# attiny_pico.net
KiCad netlist of a schematic drawn in EAGLE
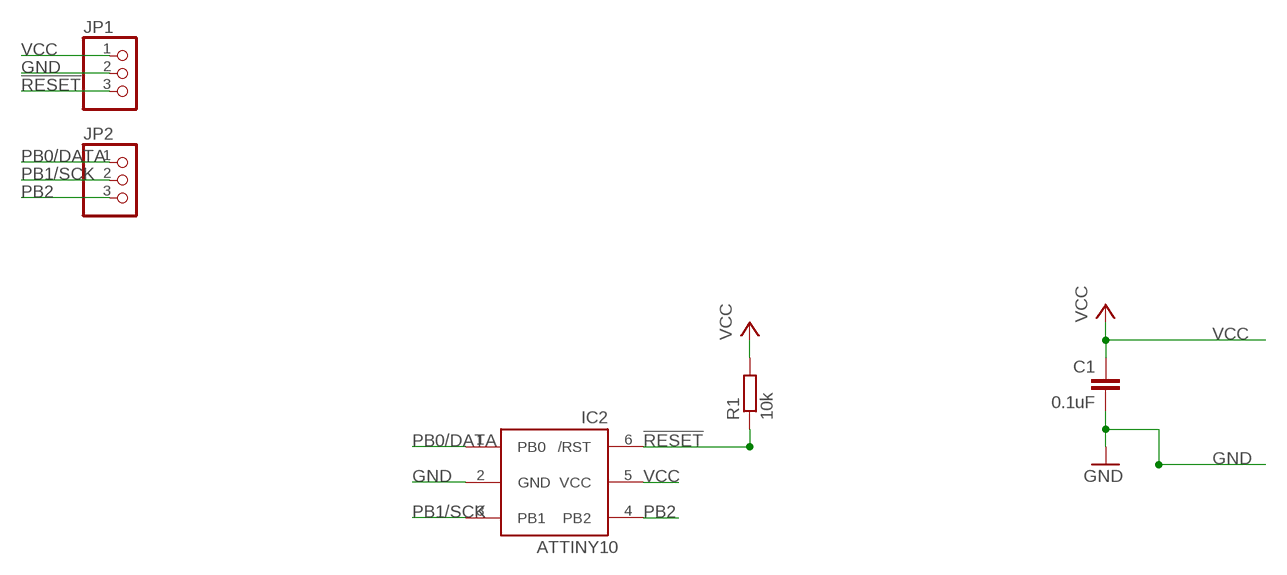
[diagram p0: schematic, sheet 1]

(export (version "E")
  (design (tool "Eeschema 10.0.6"))
  (components
    (comp (ref "C1")
      (value "0.1uF")
      (footprint "eagle-import:C0805")
      (libsource (lib "eagle-import") (part "C-EUC0805"))
    )
    (comp (ref "IC2")
      (value "ATTINY10")
      (footprint "eagle-import:SOT23-6")
      (libsource (lib "eagle-import") (part "ATTINY10"))
    )
    (comp (ref "JP1")
      (value "PINHD-1X3")
      (footprint "eagle-import:1X03")
      (libsource (lib "eagle-import") (part "PINHD-1X3"))
    )
    (comp (ref "JP2")
      (value "PINHD-1X3")
      (footprint "eagle-import:1X03")
      (libsource (lib "eagle-import") (part "PINHD-1X3"))
    )
    (comp (ref "R1")
      (value "10k")
      (footprint "eagle-import:R0805")
      (libsource (lib "eagle-import") (part "R-EU_R0805"))
    )
  )
  (nets
    (net (code "1") (name "/PB0{slash}DATA") (class "Default")
      (node (ref "IC2") (pin "1") (pinfunction "PB0_1") (pintype "bidirectional"))
      (node (ref "JP2") (pin "1") (pinfunction "1_1") (pintype "passive"))
    )
    (net (code "2") (name "/PB1{slash}SCK") (class "Default")
      (node (ref "IC2") (pin "3") (pinfunction "PB1_3") (pintype "bidirectional"))
      (node (ref "JP2") (pin "2") (pinfunction "2_2") (pintype "passive"))
    )
    (net (code "3") (name "/PB2") (class "Default")
      (node (ref "IC2") (pin "4") (pinfunction "PB2_4") (pintype "bidirectional"))
      (node (ref "JP2") (pin "3") (pinfunction "3_3") (pintype "passive"))
    )
    (net (code "4") (name "/~{RESET}") (class "Default")
      (node (ref "IC2") (pin "6") (pinfunction "/RST_6") (pintype "bidirectional"))
      (node (ref "JP1") (pin "3") (pinfunction "3_3") (pintype "passive"))
      (node (ref "R1") (pin "1") (pinfunction "1_1") (pintype "passive"))
    )
    (net (code "5") (name "GND") (class "Default")
      (node (ref "C1") (pin "2") (pinfunction "2_2") (pintype "passive"))
      (node (ref "IC2") (pin "2") (pinfunction "GND_2") (pintype "power_in"))
      (node (ref "JP1") (pin "2") (pinfunction "2_2") (pintype "passive"))
    )
    (net (code "6") (name "VCC") (class "Default")
      (node (ref "C1") (pin "1") (pinfunction "1_1") (pintype "passive"))
      (node (ref "IC2") (pin "5") (pinfunction "VCC_5") (pintype "power_in"))
      (node (ref "JP1") (pin "1") (pinfunction "1_1") (pintype "passive"))
      (node (ref "R1") (pin "2") (pinfunction "2_2") (pintype "passive"))
    )
  )
)
